# Battery_Management.net
KiCad netlist of a schematic drawn in Altium Designer
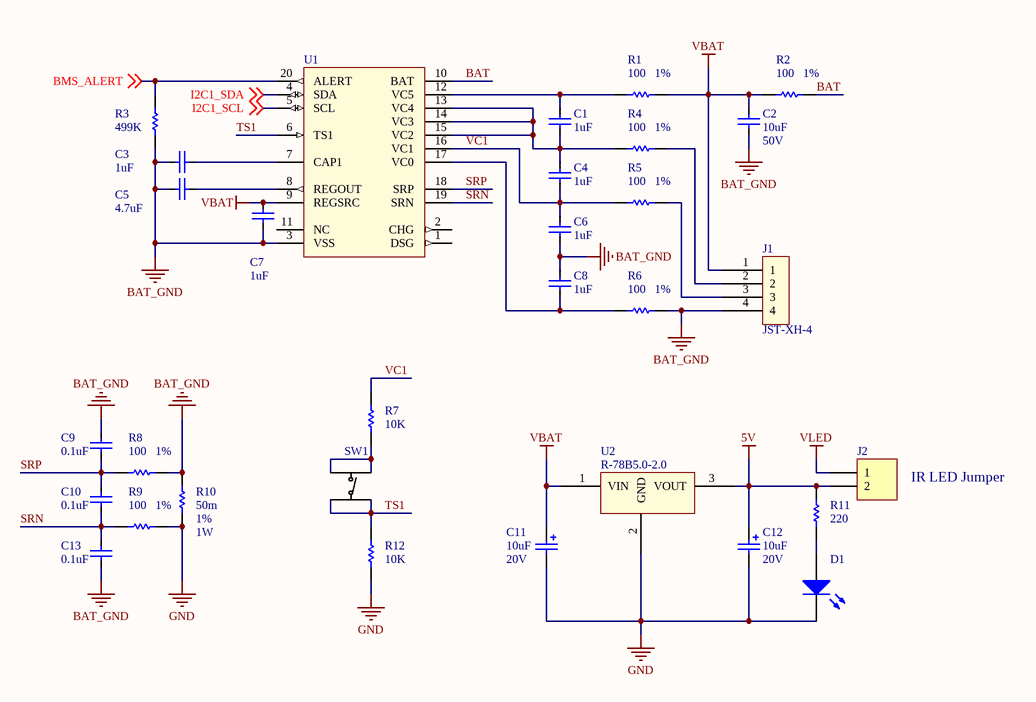
[diagram p0: Battery Management.SchDoc]

(export (version "E")
  (design (tool "Eeschema 10.0.6"))
  (components
    (comp (ref "C1")
      (value "1uF")
      (footprint "C0805")
      (description "CAP CER 1UF 25V X7R 0805")
      (fields
        (field (name "MANUFACTURER") "Murata Electronics North America")
        (field (name "MANUFACTURER PART NUMBER") "GCM21BR71E105KA56L")
      )
      (libsource (lib "Components") (part "CAP"))
    )
    (comp (ref "C2")
      (value "10uF")
      (footprint "1206")
      (description "CAP CER 10UF 50V X5R 1206")
      (fields
        (field (name "MANUFACTURER") "Murata Electronics North America")
        (field (name "MANUFACTURER PART NUMBER") "GRT31CR61H106KE01L")
        (field (name "VOLTAGE - RATED") "50V")
      )
      (libsource (lib "Components") (part "CAP"))
    )
    (comp (ref "C3")
      (value "1uF")
      (footprint "C0805")
      (description "CAP CER 1UF 25V X7R 0805")
      (fields
        (field (name "MANUFACTURER") "Murata Electronics North America")
        (field (name "MANUFACTURER PART NUMBER") "GCM21BR71E105KA56L")
      )
      (libsource (lib "Components") (part "CAP"))
    )
    (comp (ref "C4")
      (value "1uF")
      (footprint "C0805")
      (description "CAP CER 1UF 25V X7R 0805")
      (fields
        (field (name "MANUFACTURER") "Murata Electronics North America")
        (field (name "MANUFACTURER PART NUMBER") "GCM21BR71E105KA56L")
      )
      (libsource (lib "Components") (part "CAP"))
    )
    (comp (ref "C5")
      (value "4.7uF")
      (footprint "C0805")
      (description "CAP CER 4.7UF 10V X7R 0805")
      (fields
        (field (name "MANUFACTURER") "Samsung Electro-Mechanics")
        (field (name "MANUFACTURER PART NUMBER") "CL21B475KPFNNNE")
      )
      (libsource (lib "Components") (part "CAP"))
    )
    (comp (ref "C6")
      (value "1uF")
      (footprint "C0805")
      (description "CAP CER 1UF 25V X7R 0805")
      (fields
        (field (name "MANUFACTURER") "Murata Electronics North America")
        (field (name "MANUFACTURER PART NUMBER") "GCM21BR71E105KA56L")
      )
      (libsource (lib "Components") (part "CAP"))
    )
    (comp (ref "C7")
      (value "1uF")
      (footprint "C0805")
      (description "CAP CER 1UF 25V X7R 0805")
      (fields
        (field (name "MANUFACTURER") "Murata Electronics North America")
        (field (name "MANUFACTURER PART NUMBER") "GCM21BR71E105KA56L")
      )
      (libsource (lib "Components") (part "CAP"))
    )
    (comp (ref "C8")
      (value "1uF")
      (footprint "C0805")
      (description "CAP CER 1UF 25V X7R 0805")
      (fields
        (field (name "MANUFACTURER") "Murata Electronics North America")
        (field (name "MANUFACTURER PART NUMBER") "GCM21BR71E105KA56L")
      )
      (libsource (lib "Components") (part "CAP"))
    )
    (comp (ref "C9")
      (value "0.1uF")
      (footprint "J1-0603")
      (description "CAP CER 0.1UF 50V X7R 0603")
      (fields (field (name "Comment") "CAP"))
      (libsource (lib "Components") (part "CAP"))
    )
    (comp (ref "C10")
      (value "0.1uF")
      (footprint "J1-0603")
      (description "CAP CER 0.1UF 50V X7R 0603")
      (fields (field (name "Comment") "CAP"))
      (libsource (lib "Components") (part "CAP"))
    )
    (comp (ref "C11")
      (value "10uF")
      (footprint "1206+")
      (description "CAP TANT 10UF 10% 20V 1206")
      (fields
        (field (name "VOLTAGE RATING") "20V")
        (field (name "Comment") "CAP POL")
        (field (name "PUBLISHER") "Altium Limited")
      )
      (libsource (lib "MicromouseLib") (part "CAP POL"))
    )
    (comp (ref "C12")
      (value "10uF")
      (footprint "1206+")
      (description "CAP TANT 10UF 10% 20V 1206")
      (fields
        (field (name "VOLTAGE RATING") "20V")
        (field (name "Comment") "CAP POL")
        (field (name "PUBLISHER") "Altium Limited")
      )
      (libsource (lib "MicromouseLib") (part "CAP POL"))
    )
    (comp (ref "C13")
      (value "0.1uF")
      (footprint "J1-0603")
      (description "CAP CER 0.1UF 50V X7R 0603")
      (fields (field (name "Comment") "CAP"))
      (libsource (lib "Components") (part "CAP"))
    )
    (comp (ref "D1")
      (value "LED")
      (footprint "0603-DI-GREEN")
      (description "LED GREEN CLEAR CHIP SMD")
      (fields (field (name "PUBLISHER") "Altium Limited"))
      (libsource (lib "MicromouseLib") (part "LED"))
    )
    (comp (ref "J1")
      (value "JST-XH-4")
      (footprint "JST-XH-4")
      (description "CONN HEADER R/A 4POS 2.5MM")
      (fields
        (field (name "MANUFACTURER") "JST Sales America Inc.")
        (field (name "MANUFACTURER PART NUMBER") "S4B-XH-A(LF)(SN)")
      )
      (libsource (lib "MicromouseLib") (part "JST-XH-4"))
    )
    (comp (ref "J2")
      (value "Header 2")
      (footprint "HDR1X2")
      (description "Header, 2-Pin")
      (fields (field (name "PUBLISHER") "Altium Limited"))
      (libsource (lib "Miscellaneous Connectors") (part "Header 2"))
    )
    (comp (ref "R1")
      (value "100")
      (footprint "J1-0603")
      (description "RES SMD 100 OHM 1% 1/10W 0603")
      (fields (field (name "TOLERANCE") "1%"))
      (libsource (lib "Miscellaneous Devices") (part "Res1"))
    )
    (comp (ref "R2")
      (value "100")
      (footprint "J1-0603")
      (description "RES SMD 100 OHM 1% 1/10W 0603")
      (fields (field (name "TOLERANCE") "1%"))
      (libsource (lib "Miscellaneous Devices") (part "Res1"))
    )
    (comp (ref "R3")
      (value "499K")
      (footprint "J1-0603")
      (description "RES SMD 499K OHM 1% 1/10W 0603")
      (libsource (lib "Miscellaneous Devices") (part "Res1"))
    )
    (comp (ref "R4")
      (value "100")
      (footprint "J1-0603")
      (description "RES SMD 100 OHM 1% 1/10W 0603")
      (fields (field (name "TOLERANCE") "1%"))
      (libsource (lib "Miscellaneous Devices") (part "Res1"))
    )
    (comp (ref "R5")
      (value "100")
      (footprint "J1-0603")
      (description "RES SMD 100 OHM 1% 1/10W 0603")
      (fields (field (name "TOLERANCE") "1%"))
      (libsource (lib "Miscellaneous Devices") (part "Res1"))
    )
    (comp (ref "R6")
      (value "100")
      (footprint "J1-0603")
      (description "RES SMD 100 OHM 1% 1/10W 0603")
      (fields (field (name "TOLERANCE") "1%"))
      (libsource (lib "Miscellaneous Devices") (part "Res1"))
    )
    (comp (ref "R7")
      (value "10K")
      (footprint "J1-0603")
      (description "RES SMD 10K OHM 5% 1/10W 0603")
      (libsource (lib "Miscellaneous Devices") (part "Res1"))
    )
    (comp (ref "R8")
      (value "100")
      (footprint "J1-0603")
      (description "RES SMD 100 OHM 1% 1/10W 0603")
      (fields (field (name "TOLERANCE") "1%"))
      (libsource (lib "Miscellaneous Devices") (part "Res1"))
    )
    (comp (ref "R9")
      (value "100")
      (footprint "J1-0603")
      (description "RES SMD 100 OHM 1% 1/10W 0603")
      (fields (field (name "TOLERANCE") "1%"))
      (libsource (lib "Miscellaneous Devices") (part "Res1"))
    )
    (comp (ref "R10")
      (value "50m")
      (footprint "RESC6332")
      (description "RES 0.05 OHM 1% 1W 2512")
      (fields (field (name "TOLERANCE") "1%") (field (name "POWER RATING") "1W"))
      (libsource (lib "Miscellaneous Devices") (part "Res1"))
    )
    (comp (ref "R11")
      (value "220")
      (footprint "J1-0603")
      (description "RES SMD 220 OHM 5% 1/10W 0603")
      (libsource (lib "Miscellaneous Devices") (part "Res1"))
    )
    (comp (ref "R12")
      (value "10K")
      (footprint "J1-0603")
      (description "RES SMD 10K OHM 5% 1/10W 0603")
      (libsource (lib "Miscellaneous Devices") (part "Res1"))
    )
    (comp (ref "SW1")
      (value "TACT SWITCH")
      (footprint "TACT SWITCH")
      (description "SWITCH TACTILE SPST-NO 0.05A 12V")
      (fields
        (field (name "MANUFACTURER") "C&K")
        (field (name "MANUFACTURER PART NUMBER") "PTS645SL50SMTR92 LFS")
      )
      (libsource (lib "MicromouseLib") (part "TACT SWITCH"))
    )
    (comp (ref "U1")
      (value "bq76920")
      (footprint "TSSOP20")
      (description "IC BATT MGMT LI-ION AFE 20TSSOP")
      (libsource (lib "MicromouseLib") (part "bq76920"))
    )
    (comp (ref "U2")
      (value "R-78BXX-XX")
      (footprint "SIP-3")
      (description "DC DC CONVERTER 5V")
      (fields
        (field (name "MANUFACTURER") "Recom Power")
        (field (name "MANUFACTURER PART NUMBER") "R-78B5.0-2.0")
      )
      (libsource (lib "MicromouseLib") (part "R-78BXX-XX"))
    )
  )
  (nets
    (net (code "1") (name "/BAT") (class "Default")
      (node (ref "R2") (pin "1") (pinfunction "1_1") (pintype "passive"))
      (node (ref "U1") (pin "10") (pinfunction "BAT_10") (pintype "power_in"))
    )
    (net (code "2") (name "/SRN") (class "Default")
      (node (ref "C10") (pin "1") (pinfunction "1_1") (pintype "passive"))
      (node (ref "C13") (pin "2") (pinfunction "2_2") (pintype "passive"))
      (node (ref "R9") (pin "2") (pinfunction "2_2") (pintype "passive"))
      (node (ref "U1") (pin "19") (pinfunction "SRN_19") (pintype "passive"))
    )
    (net (code "3") (name "/SRP") (class "Default")
      (node (ref "C10") (pin "2") (pinfunction "2_2") (pintype "passive"))
      (node (ref "C9") (pin "1") (pinfunction "1_1") (pintype "passive"))
      (node (ref "R8") (pin "2") (pinfunction "2_2") (pintype "passive"))
      (node (ref "U1") (pin "18") (pinfunction "SRP_18") (pintype "passive"))
    )
    (net (code "4") (name "/TS1") (class "Default")
      (node (ref "R12") (pin "1") (pinfunction "1_1") (pintype "passive"))
      (node (ref "SW1") (pin "3") (pintype "power_in"))
      (node (ref "SW1") (pin "4") (pintype "power_in"))
      (node (ref "U1") (pin "6") (pinfunction "TS1_6") (pintype "input"))
    )
    (net (code "5") (name "/VC1") (class "Default")
      (node (ref "C4") (pin "1") (pinfunction "1_1") (pintype "passive"))
      (node (ref "C6") (pin "2") (pinfunction "2_2") (pintype "passive"))
      (node (ref "R5") (pin "2") (pinfunction "2_2") (pintype "passive"))
      (node (ref "R7") (pin "1") (pinfunction "1_1") (pintype "passive"))
      (node (ref "U1") (pin "16") (pinfunction "VC1_16") (pintype "passive"))
    )
    (net (code "6") (name "5V") (class "Default")
      (node (ref "C12") (pin "1") (pinfunction "1_1") (pintype "passive"))
      (node (ref "J2") (pin "2") (pinfunction "2_2") (pintype "passive"))
      (node (ref "R11") (pin "1") (pinfunction "1_1") (pintype "passive"))
      (node (ref "U2") (pin "3") (pinfunction "VOUT_3") (pintype "power_in"))
    )
    (net (code "7") (name "BAT_GND") (class "Default")
      (node (ref "C13") (pin "1") (pinfunction "1_1") (pintype "passive"))
      (node (ref "C2") (pin "2") (pinfunction "2_2") (pintype "passive"))
      (node (ref "C3") (pin "1") (pinfunction "1_1") (pintype "passive"))
      (node (ref "C5") (pin "2") (pinfunction "2_2") (pintype "passive"))
      (node (ref "C6") (pin "1") (pinfunction "1_1") (pintype "passive"))
      (node (ref "C7") (pin "1") (pinfunction "1_1") (pintype "passive"))
      (node (ref "C8") (pin "2") (pinfunction "2_2") (pintype "passive"))
      (node (ref "C9") (pin "2") (pinfunction "2_2") (pintype "passive"))
      (node (ref "J1") (pin "4") (pinfunction "4_4") (pintype "passive"))
      (node (ref "R10") (pin "1") (pinfunction "1_1") (pintype "passive"))
      (node (ref "R3") (pin "1") (pinfunction "1_1") (pintype "passive"))
      (node (ref "R6") (pin "1") (pinfunction "1_1") (pintype "passive"))
      (node (ref "R8") (pin "1") (pinfunction "1_1") (pintype "passive"))
      (node (ref "U1") (pin "3") (pinfunction "VSS_3") (pintype "power_in"))
    )
    (net (code "8") (name "BMS_ALERT") (class "Default")
      (node (ref "R3") (pin "2") (pinfunction "2_2") (pintype "passive"))
      (node (ref "U1") (pin "20") (pinfunction "ALERT_20") (pintype "output"))
    )
    (net (code "9") (name "GND") (class "Default")
      (node (ref "C11") (pin "2") (pinfunction "2_2") (pintype "passive"))
      (node (ref "C12") (pin "2") (pinfunction "2_2") (pintype "passive"))
      (node (ref "D1") (pin "2") (pinfunction "K_2") (pintype "passive"))
      (node (ref "R10") (pin "2") (pinfunction "2_2") (pintype "passive"))
      (node (ref "R12") (pin "2") (pinfunction "2_2") (pintype "passive"))
      (node (ref "R9") (pin "1") (pinfunction "1_1") (pintype "passive"))
      (node (ref "U2") (pin "2") (pinfunction "GND_2") (pintype "power_in"))
    )
    (net (code "10") (name "I2C1_SCL") (class "Default")
      (node (ref "U1") (pin "5") (pinfunction "SCL_5") (pintype "bidirectional"))
    )
    (net (code "11") (name "I2C1_SDA") (class "Default")
      (node (ref "U1") (pin "4") (pinfunction "SDA_4") (pintype "bidirectional"))
    )
    (net (code "12") (name "Net-(D1-A)") (class "Default")
      (node (ref "D1") (pin "1") (pinfunction "A_1") (pintype "passive"))
      (node (ref "R11") (pin "2") (pinfunction "2_2") (pintype "passive"))
    )
    (net (code "13") (name "Net-(J1-Pad2)") (class "Default")
      (node (ref "J1") (pin "2") (pinfunction "2_2") (pintype "passive"))
      (node (ref "R4") (pin "1") (pinfunction "1_1") (pintype "passive"))
    )
    (net (code "14") (name "Net-(J1-Pad3)") (class "Default")
      (node (ref "J1") (pin "3") (pinfunction "3_3") (pintype "passive"))
      (node (ref "R5") (pin "1") (pinfunction "1_1") (pintype "passive"))
    )
    (net (code "15") (name "Net-(R7-Pad2)") (class "Default")
      (node (ref "R7") (pin "2") (pinfunction "2_2") (pintype "passive"))
      (node (ref "SW1") (pin "1") (pintype "power_in"))
      (node (ref "SW1") (pin "2") (pintype "power_in"))
    )
    (net (code "16") (name "Net-(U1-CAP1)") (class "Default")
      (node (ref "C3") (pin "2") (pinfunction "2_2") (pintype "passive"))
      (node (ref "U1") (pin "7") (pinfunction "CAP1_7") (pintype "passive"))
    )
    (net (code "17") (name "Net-(U1-REGOUT)") (class "Default")
      (node (ref "C5") (pin "1") (pinfunction "1_1") (pintype "passive"))
      (node (ref "U1") (pin "8") (pinfunction "REGOUT_8") (pintype "output"))
    )
    (net (code "18") (name "Net-(U1-VC0)") (class "Default")
      (node (ref "C8") (pin "1") (pinfunction "1_1") (pintype "passive"))
      (node (ref "R6") (pin "2") (pinfunction "2_2") (pintype "passive"))
      (node (ref "U1") (pin "17") (pinfunction "VC0_17") (pintype "passive"))
    )
    (net (code "19") (name "Net-(U1-VC2)") (class "Default")
      (node (ref "C1") (pin "1") (pinfunction "1_1") (pintype "passive"))
      (node (ref "C4") (pin "2") (pinfunction "2_2") (pintype "passive"))
      (node (ref "R4") (pin "2") (pinfunction "2_2") (pintype "passive"))
      (node (ref "U1") (pin "13") (pinfunction "VC4_13") (pintype "passive"))
      (node (ref "U1") (pin "14") (pinfunction "VC3_14") (pintype "passive"))
      (node (ref "U1") (pin "15") (pinfunction "VC2_15") (pintype "passive"))
    )
    (net (code "20") (name "Net-(U1-VC5)") (class "Default")
      (node (ref "C1") (pin "2") (pinfunction "2_2") (pintype "passive"))
      (node (ref "R1") (pin "2") (pinfunction "2_2") (pintype "passive"))
      (node (ref "U1") (pin "12") (pinfunction "VC5_12") (pintype "passive"))
    )
    (net (code "21") (name "VBAT") (class "Default")
      (node (ref "C11") (pin "1") (pinfunction "1_1") (pintype "passive"))
      (node (ref "C2") (pin "1") (pinfunction "1_1") (pintype "passive"))
      (node (ref "C7") (pin "2") (pinfunction "2_2") (pintype "passive"))
      (node (ref "J1") (pin "1") (pinfunction "1_1") (pintype "passive"))
      (node (ref "R1") (pin "1") (pinfunction "1_1") (pintype "passive"))
      (node (ref "R2") (pin "2") (pinfunction "2_2") (pintype "passive"))
      (node (ref "U1") (pin "9") (pinfunction "REGSRC_9") (pintype "power_in"))
      (node (ref "U2") (pin "1") (pinfunction "VIN_1") (pintype "power_in"))
    )
    (net (code "22") (name "VLED") (class "Default")
      (node (ref "J2") (pin "1") (pinfunction "1_1") (pintype "passive"))
    )
    (net (code "23") (name "unconnected-(U1-CHG-Pad2)") (class "Default")
      (node (ref "U1") (pin "2") (pinfunction "CHG_2") (pintype "output"))
    )
    (net (code "24") (name "unconnected-(U1-DSG-Pad1)") (class "Default")
      (node (ref "U1") (pin "1") (pinfunction "DSG_1") (pintype "output"))
    )
    (net (code "25") (name "unconnected-(U1-NC-Pad11)") (class "Default")
      (node (ref "U1") (pin "11") (pinfunction "NC_11") (pintype "passive"))
    )
  )
)
